# EASY-EDA-QUINN.net
KiCad netlist of a schematic drawn in EasyEDA
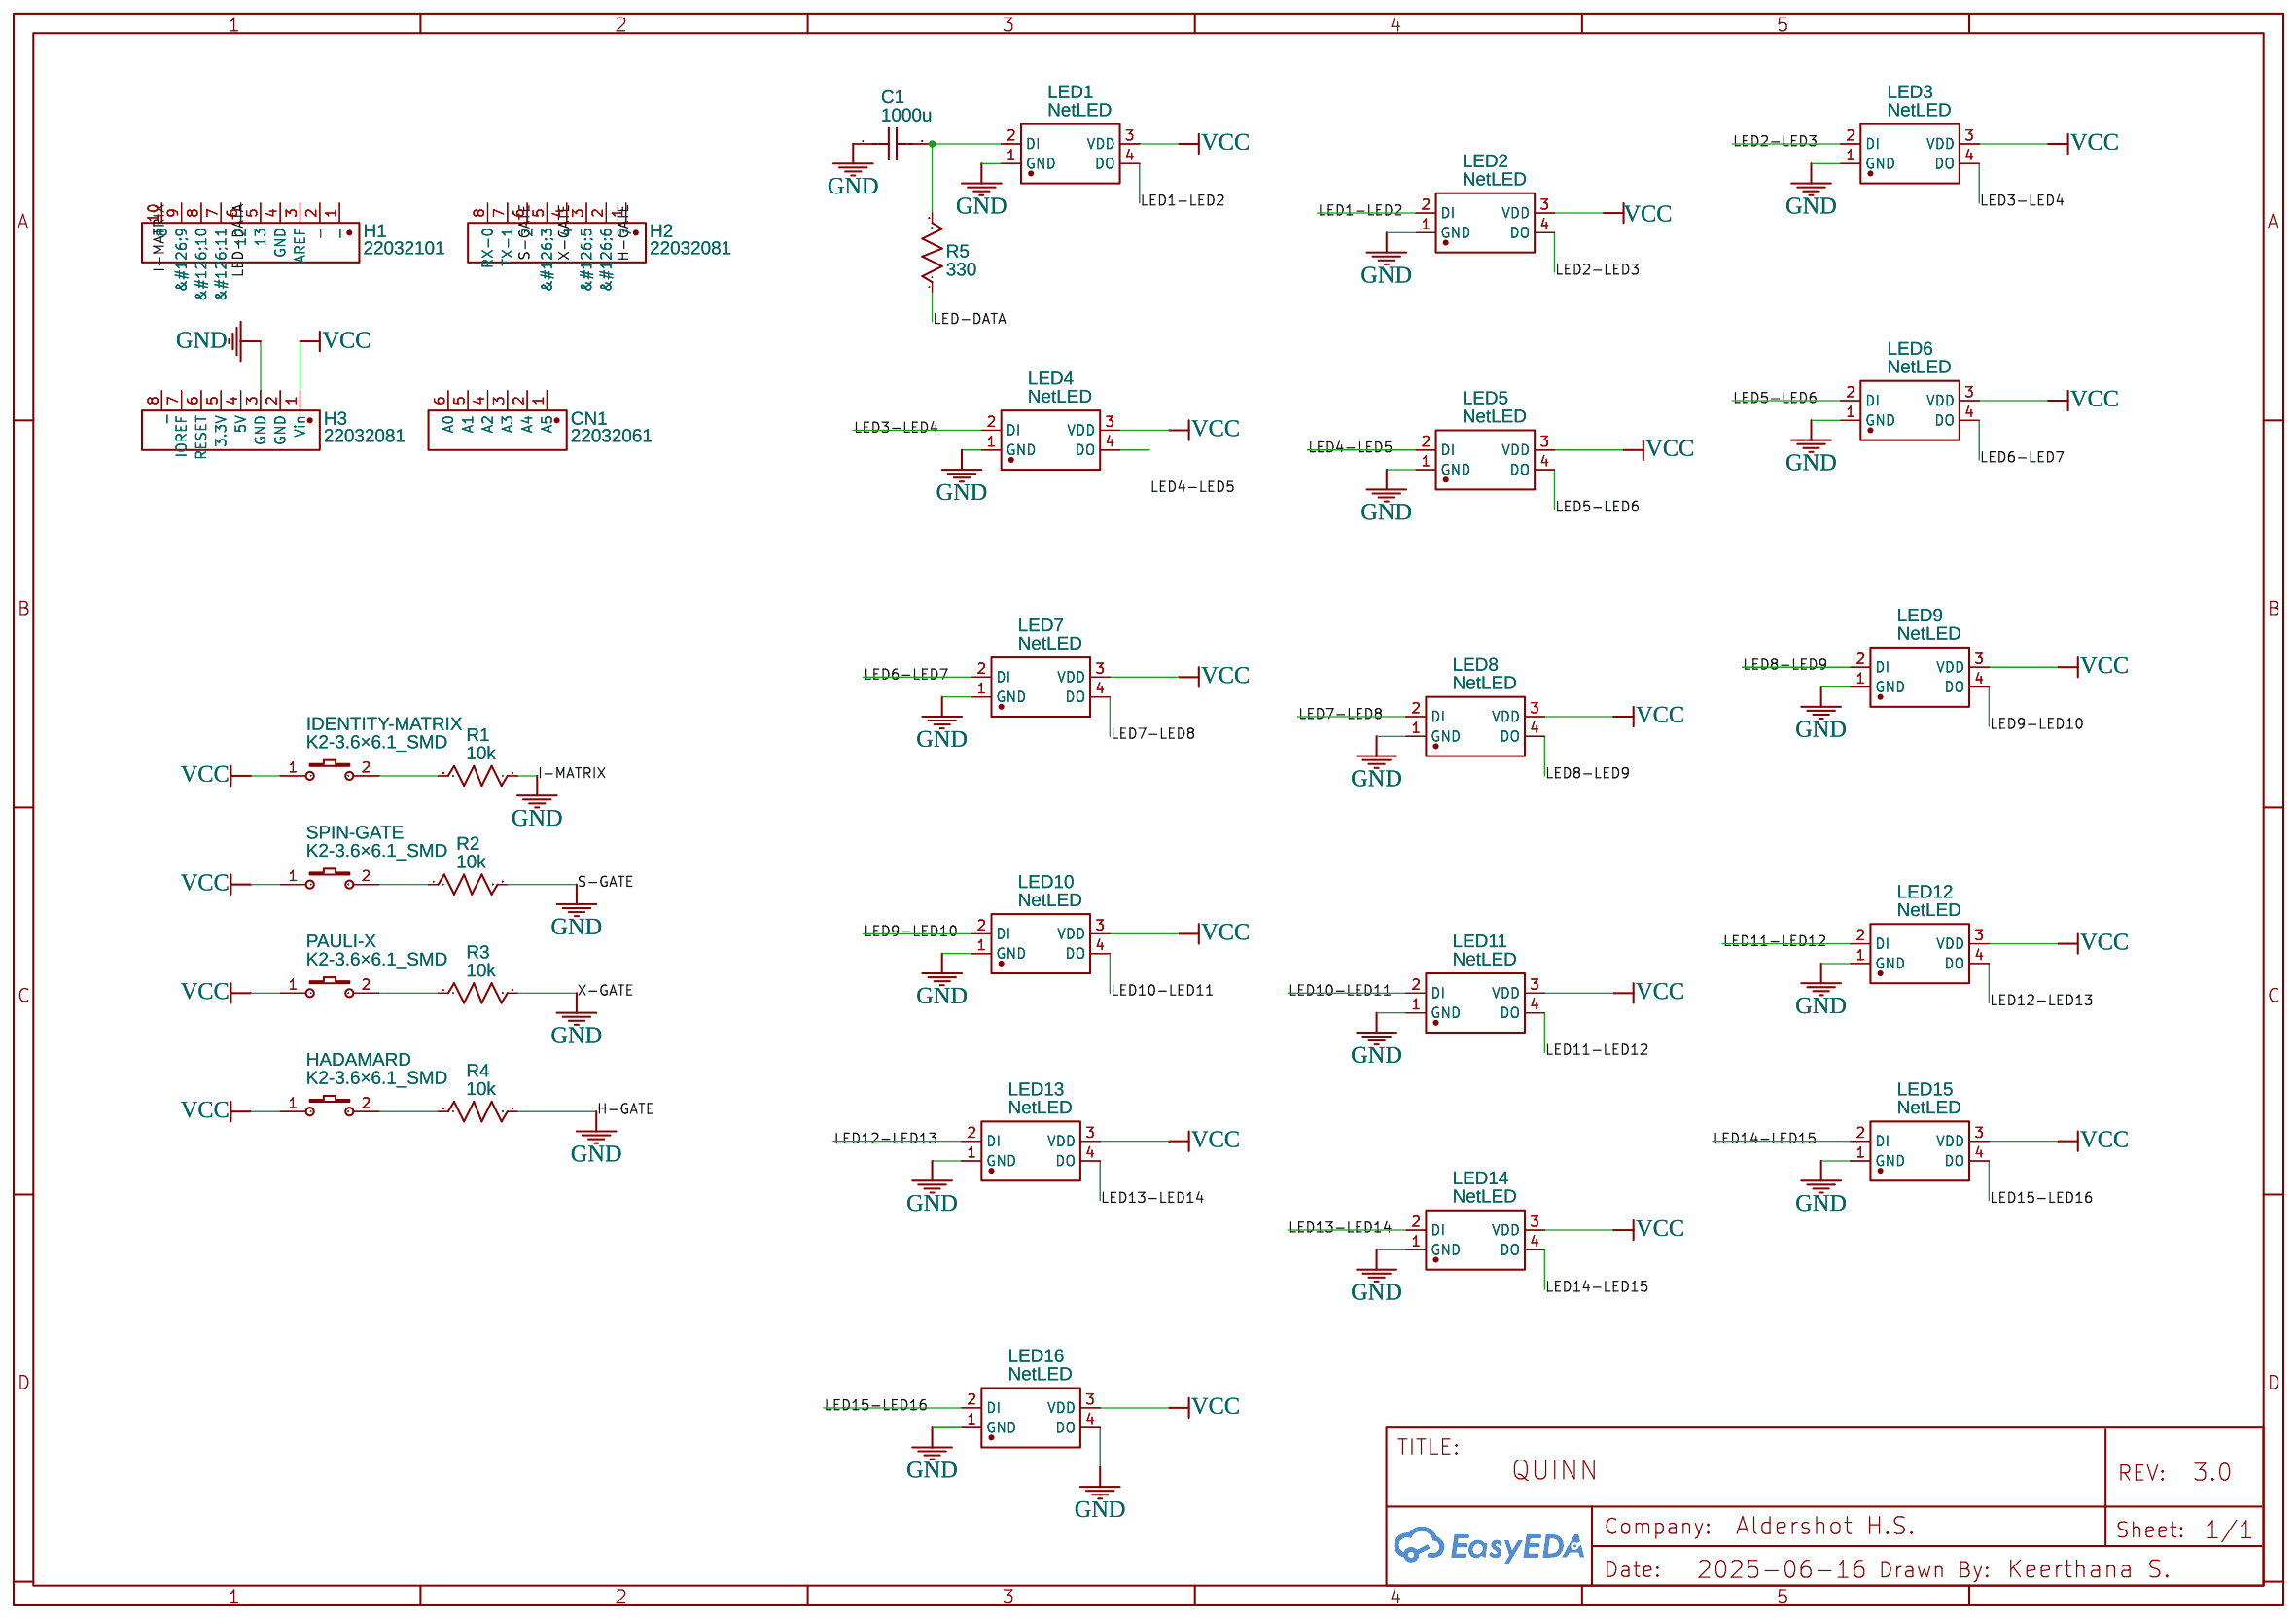
[diagram p0: schematic sheet]

(export (version "E")
  (design (tool "Eeschema 10.0.6"))
  (components
    (comp (ref "C1") (value "1000u") (libsource (lib "") (part "C_0603_US")))
    (comp (ref "CN1")
      (value "22032061")
      (fields (field (name "Manufacturer") "MOLEX"))
      (libsource (lib "") (part "22032061"))
    )
    (comp (ref "H1")
      (value "22032101")
      (fields (field (name "Manufacturer") "MOLEX"))
      (libsource (lib "") (part "22032101"))
    )
    (comp (ref "H2")
      (value "22032081")
      (fields (field (name "Manufacturer") "MOLEX"))
      (libsource (lib "") (part "22032081_1"))
    )
    (comp (ref "H3")
      (value "22032081")
      (fields (field (name "Manufacturer") "MOLEX"))
      (libsource (lib "") (part "22032081"))
    )
    (comp (ref "HADAMARD")
      (value "K2-3.6×6.1_SMD")
      (fields (field (name "Manufacturer Part") "K2-1107ST-A4SW-06"))
      (libsource (lib "") (part "K2-3.6×6.1_SMD_2"))
    )
    (comp (ref "IDENTITY-MATRIX")
      (value "K2-3.6×6.1_SMD")
      (fields (field (name "Manufacturer Part") "K2-1107ST-A4SW-06"))
      (libsource (lib "") (part "K2-3.6×6.1_SMD"))
    )
    (comp (ref "LED1")
      (value "NetLED")
      (fields
        (field (name "Manufacturer Part") "XL-6028RGBW-WS2812B")
        (field (name "Manufacturer") "XINGLIGHT(成兴光)")
      )
      (libsource (lib "") (part "XL-6028RGBW-WS2812B"))
    )
    (comp (ref "LED2")
      (value "NetLED")
      (fields
        (field (name "Manufacturer Part") "XL-6028RGBW-WS2812B")
        (field (name "Manufacturer") "XINGLIGHT(成兴光)")
      )
      (libsource (lib "") (part "XL-6028RGBW-WS2812B"))
    )
    (comp (ref "LED3")
      (value "NetLED")
      (fields
        (field (name "Manufacturer Part") "XL-6028RGBW-WS2812B")
        (field (name "Manufacturer") "XINGLIGHT(成兴光)")
      )
      (libsource (lib "") (part "XL-6028RGBW-WS2812B"))
    )
    (comp (ref "LED4")
      (value "NetLED")
      (fields
        (field (name "Manufacturer Part") "XL-6028RGBW-WS2812B")
        (field (name "Manufacturer") "XINGLIGHT(成兴光)")
      )
      (libsource (lib "") (part "XL-6028RGBW-WS2812B"))
    )
    (comp (ref "LED5")
      (value "NetLED")
      (fields
        (field (name "Manufacturer Part") "XL-6028RGBW-WS2812B")
        (field (name "Manufacturer") "XINGLIGHT(成兴光)")
      )
      (libsource (lib "") (part "XL-6028RGBW-WS2812B"))
    )
    (comp (ref "LED6")
      (value "NetLED")
      (fields
        (field (name "Manufacturer Part") "XL-6028RGBW-WS2812B")
        (field (name "Manufacturer") "XINGLIGHT(成兴光)")
      )
      (libsource (lib "") (part "XL-6028RGBW-WS2812B"))
    )
    (comp (ref "LED7")
      (value "NetLED")
      (fields
        (field (name "Manufacturer Part") "XL-6028RGBW-WS2812B")
        (field (name "Manufacturer") "XINGLIGHT(成兴光)")
      )
      (libsource (lib "") (part "XL-6028RGBW-WS2812B"))
    )
    (comp (ref "LED8")
      (value "NetLED")
      (fields
        (field (name "Manufacturer Part") "XL-6028RGBW-WS2812B")
        (field (name "Manufacturer") "XINGLIGHT(成兴光)")
      )
      (libsource (lib "") (part "XL-6028RGBW-WS2812B"))
    )
    (comp (ref "LED9")
      (value "NetLED")
      (fields
        (field (name "Manufacturer Part") "XL-6028RGBW-WS2812B")
        (field (name "Manufacturer") "XINGLIGHT(成兴光)")
      )
      (libsource (lib "") (part "XL-6028RGBW-WS2812B"))
    )
    (comp (ref "LED10")
      (value "NetLED")
      (fields
        (field (name "Manufacturer Part") "XL-6028RGBW-WS2812B")
        (field (name "Manufacturer") "XINGLIGHT(成兴光)")
      )
      (libsource (lib "") (part "XL-6028RGBW-WS2812B"))
    )
    (comp (ref "LED11")
      (value "NetLED")
      (fields
        (field (name "Manufacturer Part") "XL-6028RGBW-WS2812B")
        (field (name "Manufacturer") "XINGLIGHT(成兴光)")
      )
      (libsource (lib "") (part "XL-6028RGBW-WS2812B"))
    )
    (comp (ref "LED12")
      (value "NetLED")
      (fields
        (field (name "Manufacturer Part") "XL-6028RGBW-WS2812B")
        (field (name "Manufacturer") "XINGLIGHT(成兴光)")
      )
      (libsource (lib "") (part "XL-6028RGBW-WS2812B"))
    )
    (comp (ref "LED13")
      (value "NetLED")
      (fields
        (field (name "Manufacturer Part") "XL-6028RGBW-WS2812B")
        (field (name "Manufacturer") "XINGLIGHT(成兴光)")
      )
      (libsource (lib "") (part "XL-6028RGBW-WS2812B"))
    )
    (comp (ref "LED14")
      (value "NetLED")
      (fields
        (field (name "Manufacturer Part") "XL-6028RGBW-WS2812B")
        (field (name "Manufacturer") "XINGLIGHT(成兴光)")
      )
      (libsource (lib "") (part "XL-6028RGBW-WS2812B"))
    )
    (comp (ref "LED15")
      (value "NetLED")
      (fields
        (field (name "Manufacturer Part") "XL-6028RGBW-WS2812B")
        (field (name "Manufacturer") "XINGLIGHT(成兴光)")
      )
      (libsource (lib "") (part "XL-6028RGBW-WS2812B"))
    )
    (comp (ref "LED16")
      (value "NetLED")
      (fields
        (field (name "Manufacturer Part") "XL-6028RGBW-WS2812B")
        (field (name "Manufacturer") "XINGLIGHT(成兴光)")
      )
      (libsource (lib "") (part "XL-6028RGBW-WS2812B"))
    )
    (comp (ref "PAULI-X")
      (value "K2-3.6×6.1_SMD")
      (fields (field (name "Manufacturer Part") "K2-1107ST-A4SW-06"))
      (libsource (lib "") (part "K2-3.6×6.1_SMD_1"))
    )
    (comp (ref "R1") (value "10k") (libsource (lib "") (part "R_0603_US_2")))
    (comp (ref "R2") (value "10k") (libsource (lib "") (part "R_0603_US")))
    (comp (ref "R3") (value "10k") (libsource (lib "") (part "R_0603_US")))
    (comp (ref "R4") (value "10k") (libsource (lib "") (part "R_0603_US")))
    (comp (ref "R5") (value "330") (libsource (lib "") (part "R_0603_US_1")))
    (comp (ref "SPIN-GATE")
      (value "K2-3.6×6.1_SMD")
      (fields (field (name "Manufacturer Part") "K2-1107ST-A4SW-06"))
      (libsource (lib "") (part "K2-3.6×6.1_SMD_3"))
    )
  )
  (nets
    (net (code "1") (name "/LED-DATA") (class "Default")
      (node (ref "H1") (pin "6") (pinfunction "12_6") (pintype "unspecified"))
      (node (ref "R5") (pin "1") (pinfunction "1_1") (pintype "unspecified"))
    )
    (net (code "2") (name "/LED1-LED2") (class "Default")
      (node (ref "LED1") (pin "4") (pinfunction "DO_4") (pintype "unspecified"))
      (node (ref "LED2") (pin "2") (pinfunction "DI_2") (pintype "unspecified"))
    )
    (net (code "3") (name "/LED2-LED3") (class "Default")
      (node (ref "LED2") (pin "4") (pinfunction "DO_4") (pintype "unspecified"))
      (node (ref "LED3") (pin "2") (pinfunction "DI_2") (pintype "unspecified"))
    )
    (net (code "4") (name "/LED3-LED4") (class "Default")
      (node (ref "LED3") (pin "4") (pinfunction "DO_4") (pintype "unspecified"))
      (node (ref "LED4") (pin "2") (pinfunction "DI_2") (pintype "unspecified"))
    )
    (net (code "5") (name "/LED4-LED5") (class "Default")
      (node (ref "LED5") (pin "2") (pinfunction "DI_2") (pintype "unspecified"))
    )
    (net (code "6") (name "/LED5-LED6") (class "Default")
      (node (ref "LED5") (pin "4") (pinfunction "DO_4") (pintype "unspecified"))
      (node (ref "LED6") (pin "2") (pinfunction "DI_2") (pintype "unspecified"))
    )
    (net (code "7") (name "/LED6-LED7") (class "Default")
      (node (ref "LED6") (pin "4") (pinfunction "DO_4") (pintype "unspecified"))
      (node (ref "LED7") (pin "2") (pinfunction "DI_2") (pintype "unspecified"))
    )
    (net (code "8") (name "/LED7-LED8") (class "Default")
      (node (ref "LED7") (pin "4") (pinfunction "DO_4") (pintype "unspecified"))
      (node (ref "LED8") (pin "2") (pinfunction "DI_2") (pintype "unspecified"))
    )
    (net (code "9") (name "/LED8-LED9") (class "Default")
      (node (ref "LED8") (pin "4") (pinfunction "DO_4") (pintype "unspecified"))
      (node (ref "LED9") (pin "2") (pinfunction "DI_2") (pintype "unspecified"))
    )
    (net (code "10") (name "/LED9-LED10") (class "Default")
      (node (ref "LED10") (pin "2") (pinfunction "DI_2") (pintype "unspecified"))
      (node (ref "LED9") (pin "4") (pinfunction "DO_4") (pintype "unspecified"))
    )
    (net (code "11") (name "/LED10-LED11") (class "Default")
      (node (ref "LED10") (pin "4") (pinfunction "DO_4") (pintype "unspecified"))
      (node (ref "LED11") (pin "2") (pinfunction "DI_2") (pintype "unspecified"))
    )
    (net (code "12") (name "/LED11-LED12") (class "Default")
      (node (ref "LED11") (pin "4") (pinfunction "DO_4") (pintype "unspecified"))
      (node (ref "LED12") (pin "2") (pinfunction "DI_2") (pintype "unspecified"))
    )
    (net (code "13") (name "/LED12-LED13") (class "Default")
      (node (ref "LED12") (pin "4") (pinfunction "DO_4") (pintype "unspecified"))
      (node (ref "LED13") (pin "2") (pinfunction "DI_2") (pintype "unspecified"))
    )
    (net (code "14") (name "/LED13-LED14") (class "Default")
      (node (ref "LED13") (pin "4") (pinfunction "DO_4") (pintype "unspecified"))
      (node (ref "LED14") (pin "2") (pinfunction "DI_2") (pintype "unspecified"))
    )
    (net (code "15") (name "/LED14-LED15") (class "Default")
      (node (ref "LED14") (pin "4") (pinfunction "DO_4") (pintype "unspecified"))
      (node (ref "LED15") (pin "2") (pinfunction "DI_2") (pintype "unspecified"))
    )
    (net (code "16") (name "/LED15-LED16") (class "Default")
      (node (ref "LED15") (pin "4") (pinfunction "DO_4") (pintype "unspecified"))
      (node (ref "LED16") (pin "2") (pinfunction "DI_2") (pintype "unspecified"))
    )
    (net (code "17") (name "GND") (class "Default")
      (node (ref "C1") (pin "1") (pinfunction "1_1") (pintype "unspecified"))
      (node (ref "H1") (pin "10") (pinfunction "8_10") (pintype "unspecified"))
      (node (ref "H2") (pin "1") (pinfunction "7_1") (pintype "unspecified"))
      (node (ref "H2") (pin "4") (pinfunction "4_4") (pintype "unspecified"))
      (node (ref "H2") (pin "6") (pinfunction "2_6") (pintype "unspecified"))
      (node (ref "H3") (pin "3") (pinfunction "GND_3") (pintype "unspecified"))
      (node (ref "LED1") (pin "1") (pinfunction "GND_1") (pintype "unspecified"))
      (node (ref "LED10") (pin "1") (pinfunction "GND_1") (pintype "unspecified"))
      (node (ref "LED11") (pin "1") (pinfunction "GND_1") (pintype "unspecified"))
      (node (ref "LED12") (pin "1") (pinfunction "GND_1") (pintype "unspecified"))
      (node (ref "LED13") (pin "1") (pinfunction "GND_1") (pintype "unspecified"))
      (node (ref "LED14") (pin "1") (pinfunction "GND_1") (pintype "unspecified"))
      (node (ref "LED15") (pin "1") (pinfunction "GND_1") (pintype "unspecified"))
      (node (ref "LED16") (pin "1") (pinfunction "GND_1") (pintype "unspecified"))
      (node (ref "LED16") (pin "4") (pinfunction "DO_4") (pintype "unspecified"))
      (node (ref "LED2") (pin "1") (pinfunction "GND_1") (pintype "unspecified"))
      (node (ref "LED3") (pin "1") (pinfunction "GND_1") (pintype "unspecified"))
      (node (ref "LED4") (pin "1") (pinfunction "GND_1") (pintype "unspecified"))
      (node (ref "LED5") (pin "1") (pinfunction "GND_1") (pintype "unspecified"))
      (node (ref "LED6") (pin "1") (pinfunction "GND_1") (pintype "unspecified"))
      (node (ref "LED7") (pin "1") (pinfunction "GND_1") (pintype "unspecified"))
      (node (ref "LED8") (pin "1") (pinfunction "GND_1") (pintype "unspecified"))
      (node (ref "LED9") (pin "1") (pinfunction "GND_1") (pintype "unspecified"))
      (node (ref "R1") (pin "1") (pinfunction "1_1") (pintype "unspecified"))
      (node (ref "R2") (pin "2") (pinfunction "2_2") (pintype "unspecified"))
      (node (ref "R3") (pin "2") (pinfunction "2_2") (pintype "unspecified"))
      (node (ref "R4") (pin "2") (pinfunction "2_2") (pintype "unspecified"))
    )
    (net (code "18") (name "Net-(HADAMARD-Pad2)") (class "Default")
      (node (ref "HADAMARD") (pin "2") (pinfunction "2_2") (pintype "unspecified"))
      (node (ref "R4") (pin "1") (pinfunction "1_1") (pintype "unspecified"))
    )
    (net (code "19") (name "Net-(IDENTITY-MATRIX-Pad2)") (class "Default")
      (node (ref "IDENTITY-MATRIX") (pin "2") (pinfunction "2_2") (pintype "unspecified"))
      (node (ref "R1") (pin "2") (pinfunction "2_2") (pintype "unspecified"))
    )
    (net (code "20") (name "Net-(LED1-DI)") (class "Default")
      (node (ref "C1") (pin "2") (pinfunction "2_2") (pintype "unspecified"))
      (node (ref "LED1") (pin "2") (pinfunction "DI_2") (pintype "unspecified"))
      (node (ref "R5") (pin "2") (pinfunction "2_2") (pintype "unspecified"))
    )
    (net (code "21") (name "Net-(PAULI-X-Pad2)") (class "Default")
      (node (ref "PAULI-X") (pin "2") (pinfunction "2_2") (pintype "unspecified"))
      (node (ref "R3") (pin "1") (pinfunction "1_1") (pintype "unspecified"))
    )
    (net (code "22") (name "Net-(R2-Pad1)") (class "Default")
      (node (ref "R2") (pin "1") (pinfunction "1_1") (pintype "unspecified"))
      (node (ref "SPIN-GATE") (pin "2") (pinfunction "2_2") (pintype "unspecified"))
    )
    (net (code "23") (name "VCC") (class "Default")
      (node (ref "H3") (pin "1") (pinfunction "Vin_1") (pintype "unspecified"))
      (node (ref "HADAMARD") (pin "1") (pinfunction "1_1") (pintype "unspecified"))
      (node (ref "IDENTITY-MATRIX") (pin "1") (pinfunction "1_1") (pintype "unspecified"))
      (node (ref "LED1") (pin "3") (pinfunction "VDD_3") (pintype "unspecified"))
      (node (ref "LED10") (pin "3") (pinfunction "VDD_3") (pintype "unspecified"))
      (node (ref "LED11") (pin "3") (pinfunction "VDD_3") (pintype "unspecified"))
      (node (ref "LED12") (pin "3") (pinfunction "VDD_3") (pintype "unspecified"))
      (node (ref "LED13") (pin "3") (pinfunction "VDD_3") (pintype "unspecified"))
      (node (ref "LED14") (pin "3") (pinfunction "VDD_3") (pintype "unspecified"))
      (node (ref "LED15") (pin "3") (pinfunction "VDD_3") (pintype "unspecified"))
      (node (ref "LED16") (pin "3") (pinfunction "VDD_3") (pintype "unspecified"))
      (node (ref "LED2") (pin "3") (pinfunction "VDD_3") (pintype "unspecified"))
      (node (ref "LED3") (pin "3") (pinfunction "VDD_3") (pintype "unspecified"))
      (node (ref "LED4") (pin "3") (pinfunction "VDD_3") (pintype "unspecified"))
      (node (ref "LED5") (pin "3") (pinfunction "VDD_3") (pintype "unspecified"))
      (node (ref "LED6") (pin "3") (pinfunction "VDD_3") (pintype "unspecified"))
      (node (ref "LED7") (pin "3") (pinfunction "VDD_3") (pintype "unspecified"))
      (node (ref "LED8") (pin "3") (pinfunction "VDD_3") (pintype "unspecified"))
      (node (ref "LED9") (pin "3") (pinfunction "VDD_3") (pintype "unspecified"))
      (node (ref "PAULI-X") (pin "1") (pinfunction "1_1") (pintype "unspecified"))
      (node (ref "SPIN-GATE") (pin "1") (pinfunction "1_1") (pintype "unspecified"))
    )
    (net (code "24") (name "unconnected-(CN1-A0-Pad6)") (class "Default")
      (node (ref "CN1") (pin "6") (pinfunction "A0_6") (pintype "unspecified"))
    )
    (net (code "25") (name "unconnected-(CN1-A1-Pad5)") (class "Default")
      (node (ref "CN1") (pin "5") (pinfunction "A1_5") (pintype "unspecified"))
    )
    (net (code "26") (name "unconnected-(CN1-A2-Pad4)") (class "Default")
      (node (ref "CN1") (pin "4") (pinfunction "A2_4") (pintype "unspecified"))
    )
    (net (code "27") (name "unconnected-(CN1-A3-Pad3)") (class "Default")
      (node (ref "CN1") (pin "3") (pinfunction "A3_3") (pintype "unspecified"))
    )
    (net (code "28") (name "unconnected-(CN1-A4-Pad2)") (class "Default")
      (node (ref "CN1") (pin "2") (pinfunction "A4_2") (pintype "unspecified"))
    )
    (net (code "29") (name "unconnected-(CN1-A5-Pad1)") (class "Default")
      (node (ref "CN1") (pin "1") (pinfunction "A5_1") (pintype "unspecified"))
    )
    (net (code "30") (name "unconnected-(H1-&#126;9-Pad9)") (class "Default")
      (node (ref "H1") (pin "9") (pinfunction "&#126;9_9") (pintype "unspecified"))
    )
    (net (code "31") (name "unconnected-(H1-&#126;10-Pad8)") (class "Default")
      (node (ref "H1") (pin "8") (pinfunction "&#126;10_8") (pintype "unspecified"))
    )
    (net (code "32") (name "unconnected-(H1-&#126;11-Pad7)") (class "Default")
      (node (ref "H1") (pin "7") (pinfunction "&#126;11_7") (pintype "unspecified"))
    )
    (net (code "33") (name "unconnected-(H1---Pad1)") (class "Default")
      (node (ref "H1") (pin "1") (pinfunction "-_1") (pintype "unspecified"))
    )
    (net (code "34") (name "unconnected-(H1---Pad2)") (class "Default")
      (node (ref "H1") (pin "2") (pinfunction "-_2") (pintype "unspecified"))
    )
    (net (code "35") (name "unconnected-(H1-13-Pad5)") (class "Default")
      (node (ref "H1") (pin "5") (pinfunction "13_5") (pintype "unspecified"))
    )
    (net (code "36") (name "unconnected-(H1-AREF-Pad3)") (class "Default")
      (node (ref "H1") (pin "3") (pinfunction "AREF_3") (pintype "unspecified"))
    )
    (net (code "37") (name "unconnected-(H1-GND-Pad4)") (class "Default")
      (node (ref "H1") (pin "4") (pinfunction "GND_4") (pintype "unspecified"))
    )
    (net (code "38") (name "unconnected-(H2-&#126;3-Pad5)") (class "Default")
      (node (ref "H2") (pin "5") (pinfunction "&#126;3_5") (pintype "unspecified"))
    )
    (net (code "39") (name "unconnected-(H2-&#126;5-Pad3)") (class "Default")
      (node (ref "H2") (pin "3") (pinfunction "&#126;5_3") (pintype "unspecified"))
    )
    (net (code "40") (name "unconnected-(H2-&#126;6-Pad2)") (class "Default")
      (node (ref "H2") (pin "2") (pinfunction "&#126;6_2") (pintype "unspecified"))
    )
    (net (code "41") (name "unconnected-(H2-RX-0-Pad8)") (class "Default")
      (node (ref "H2") (pin "8") (pinfunction "RX-0_8") (pintype "unspecified"))
    )
    (net (code "42") (name "unconnected-(H2-TX-1-Pad7)") (class "Default")
      (node (ref "H2") (pin "7") (pinfunction "TX-1_7") (pintype "unspecified"))
    )
    (net (code "43") (name "unconnected-(H3-3.3V-Pad5)") (class "Default")
      (node (ref "H3") (pin "5") (pinfunction "3.3V_5") (pintype "unspecified"))
    )
    (net (code "44") (name "unconnected-(H3-5V-Pad4)") (class "Default")
      (node (ref "H3") (pin "4") (pinfunction "5V_4") (pintype "unspecified"))
    )
    (net (code "45") (name "unconnected-(H3-GND-Pad2)") (class "Default")
      (node (ref "H3") (pin "2") (pinfunction "GND_2") (pintype "unspecified"))
    )
    (net (code "46") (name "unconnected-(H3-IOREF-Pad7)") (class "Default")
      (node (ref "H3") (pin "7") (pinfunction "IOREF_7") (pintype "unspecified"))
    )
    (net (code "47") (name "unconnected-(H3-RESET-Pad6)") (class "Default")
      (node (ref "H3") (pin "6") (pinfunction "RESET_6") (pintype "unspecified"))
    )
    (net (code "48") (name "unconnected-(H3-_-Pad8)") (class "Default")
      (node (ref "H3") (pin "8") (pinfunction "__8") (pintype "unspecified"))
    )
    (net (code "49") (name "unconnected-(LED4-DO-Pad4)") (class "Default")
      (node (ref "LED4") (pin "4") (pinfunction "DO_4") (pintype "unspecified"))
    )
  )
)
